# Open_lid.net
KiCad netlist of a schematic drawn in Altium Designer
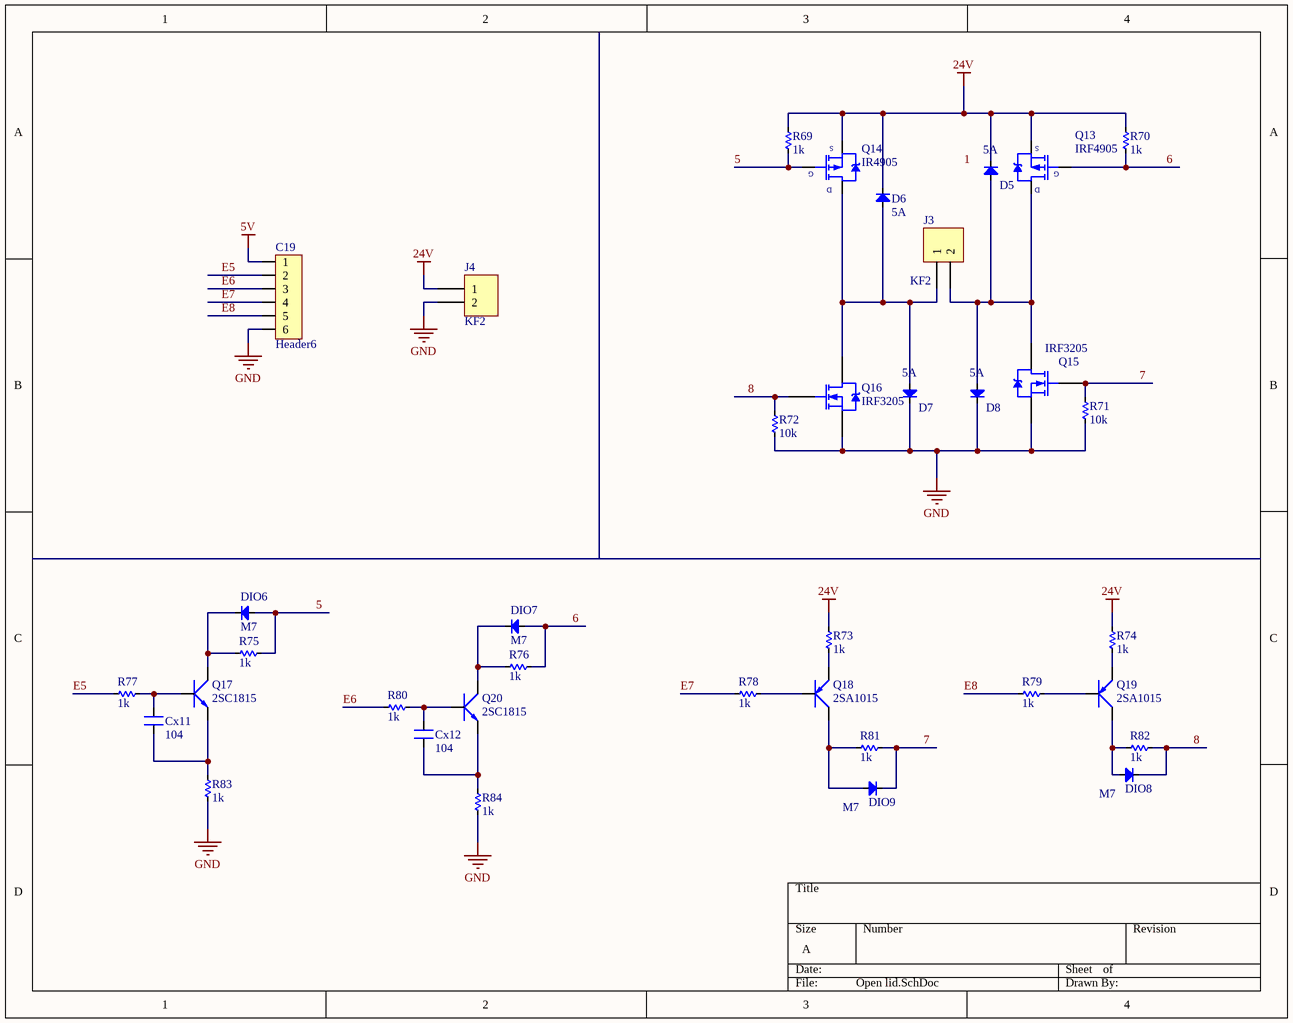
[diagram p0: Open lid.SchDoc]

(export (version "E")
  (design (tool "Eeschema 10.0.6"))
  (components
    (comp (ref "C19")
      (value "Header6")
      (footprint "HDR6")
      (description "Header IDC, 6 x 1 Pin Vertical 2.54mm Pitch (Non-Boxed, Male)")
      (fields
        (field (name "MANUFACTURER") "Würth Elektronik eiSos GmbH")
        (field (name "PARTNO") "613002143121")
        (field (name "CREATED BY") "Karrer Zheng")
      )
      (libsource (lib "LIBRARY") (part "Header6"))
    )
    (comp (ref "Cx11") (value "104") (footprint "CN-SMD-0805") (libsource (lib "LIBRARY") (part "CN")))
    (comp (ref "Cx12") (value "104") (footprint "CN-SMD-0805") (libsource (lib "LIBRARY") (part "CN")))
    (comp (ref "D5")
      (value "5A")
      (footprint "DIO-5A")
      (description "Default Diode")
      (fields (field (name "PUBLISHER") "Altium Limited"))
      (libsource (lib "LIBRARY") (part "Diode"))
    )
    (comp (ref "D6")
      (value "5A")
      (footprint "DIO-5A")
      (description "Default Diode")
      (fields (field (name "PUBLISHER") "Altium Limited"))
      (libsource (lib "LIBRARY") (part "Diode"))
    )
    (comp (ref "D7")
      (value "5A")
      (footprint "DIO-5A")
      (description "Default Diode")
      (fields (field (name "PUBLISHER") "Altium Limited"))
      (libsource (lib "LIBRARY") (part "Diode"))
    )
    (comp (ref "D8")
      (value "5A")
      (footprint "DIO-5A")
      (description "Default Diode")
      (fields (field (name "PUBLISHER") "Altium Limited"))
      (libsource (lib "LIBRARY") (part "Diode"))
    )
    (comp (ref "DIO6")
      (value "M7")
      (footprint "DIO-SMD-106")
      (description "Default Diode")
      (fields (field (name "PUBLISHER") "Altium Limited"))
      (libsource (lib "LIBRARY") (part "Diode SMD"))
    )
    (comp (ref "DIO7")
      (value "M7")
      (footprint "DIO-SMD-106")
      (description "Default Diode")
      (fields (field (name "PUBLISHER") "Altium Limited"))
      (libsource (lib "LIBRARY") (part "Diode SMD"))
    )
    (comp (ref "DIO8")
      (value "M7")
      (footprint "DIO-SMD-106")
      (description "Default Diode")
      (fields (field (name "PUBLISHER") "Altium Limited"))
      (libsource (lib "LIBRARY") (part "Diode SMD"))
    )
    (comp (ref "DIO9")
      (value "M7")
      (footprint "DIO-SMD-106")
      (description "Default Diode")
      (fields (field (name "PUBLISHER") "Altium Limited"))
      (libsource (lib "LIBRARY") (part "Diode SMD"))
    )
    (comp (ref "J3")
      (value "KF2")
      (footprint "KF2-7.62")
      (fields
        (field (name "MANUFACTURER") "Würth Elektronik eiSos GmbH")
        (field (name "PARTNO") "691103110002")
        (field (name "CREATED BY") "Karrer Zheng")
      )
      (libsource (lib "LIBRARY") (part "KF2"))
    )
    (comp (ref "J4")
      (value "KF2")
      (footprint "KF2-7.62")
      (fields
        (field (name "MANUFACTURER") "Würth Elektronik eiSos GmbH")
        (field (name "PARTNO") "691103110002")
        (field (name "CREATED BY") "Karrer Zheng")
      )
      (libsource (lib "") (part "KF2_1"))
    )
    (comp (ref "Q13")
      (value "IRF4905")
      (footprint "TO220-123")
      (description "HEXFET P-Channel Power MOSFET")
      (libsource (lib "LIBRARY") (part "IRF9540"))
    )
    (comp (ref "Q14")
      (value "IR4905")
      (footprint "TO220-123")
      (description "HEXFET P-Channel Power MOSFET")
      (libsource (lib "LIBRARY") (part "IRF9540"))
    )
    (comp (ref "Q15") (value "IRF3205") (footprint "TO220-123") (libsource (lib "LIBRARY") (part "IRFZ44")))
    (comp (ref "Q16") (value "IRF3205") (footprint "TO220-123") (libsource (lib "LIBRARY") (part "IRFZ44")))
    (comp (ref "Q17")
      (value "2SC1815")
      (footprint "SOT23-321")
      (description "NPN 600mW, ECB")
      (libsource (lib "LIBRARY") (part "2SC1815"))
    )
    (comp (ref "Q18")
      (value "2SA1015")
      (footprint "SOT23-321")
      (description "PNP 600mW, ECB")
      (libsource (lib "LIBRARY") (part "2SA1015"))
    )
    (comp (ref "Q19")
      (value "2SA1015")
      (footprint "SOT23-321")
      (description "PNP 600mW, ECB")
      (libsource (lib "LIBRARY") (part "2SA1015"))
    )
    (comp (ref "Q20")
      (value "2SC1815")
      (footprint "SOT23-321")
      (description "NPN 600mW, ECB")
      (libsource (lib "LIBRARY") (part "2SC1815"))
    )
    (comp (ref "R69")
      (value "1k")
      (footprint "RES-1/4W-SMALL")
      (description "Res")
      (fields
        (field (name "MANUFACTURER") "Generic Components")
        (field (name "PUBLISHER") "Altium Hobart Technology Centre")
      )
      (libsource (lib "LIBRARY") (part "Res"))
    )
    (comp (ref "R70")
      (value "1k")
      (footprint "RES-1/4W-SMALL")
      (description "Res")
      (fields
        (field (name "MANUFACTURER") "Generic Components")
        (field (name "PUBLISHER") "Altium Hobart Technology Centre")
      )
      (libsource (lib "LIBRARY") (part "Res"))
    )
    (comp (ref "R71")
      (value "10k")
      (footprint "RES-1/4W-SMALL")
      (description "Res")
      (fields
        (field (name "MANUFACTURER") "Generic Components")
        (field (name "PUBLISHER") "Altium Hobart Technology Centre")
      )
      (libsource (lib "LIBRARY") (part "Res"))
    )
    (comp (ref "R72")
      (value "10k")
      (footprint "RES-1/4W-SMALL")
      (description "Res")
      (fields
        (field (name "MANUFACTURER") "Generic Components")
        (field (name "PUBLISHER") "Altium Hobart Technology Centre")
      )
      (libsource (lib "LIBRARY") (part "Res"))
    )
    (comp (ref "R73")
      (value "1k")
      (footprint "RES-SMD-0805")
      (description "Resistor")
      (fields
        (field (name "MANUFACTURER") "Generic Components")
        (field (name "PUBLISHER") "Altium Hobart Technology Centre")
      )
      (libsource (lib "LIBRARY") (part "Res-SMD"))
    )
    (comp (ref "R74")
      (value "1k")
      (footprint "RES-SMD-0805")
      (description "Resistor")
      (fields
        (field (name "MANUFACTURER") "Generic Components")
        (field (name "PUBLISHER") "Altium Hobart Technology Centre")
      )
      (libsource (lib "LIBRARY") (part "Res-SMD"))
    )
    (comp (ref "R75")
      (value "1k")
      (footprint "RES-SMD-0805")
      (description "Resistor")
      (fields
        (field (name "MANUFACTURER") "Generic Components")
        (field (name "PUBLISHER") "Altium Hobart Technology Centre")
      )
      (libsource (lib "LIBRARY") (part "Res-SMD"))
    )
    (comp (ref "R76")
      (value "1k")
      (footprint "RES-SMD-0805")
      (description "Resistor")
      (fields
        (field (name "MANUFACTURER") "Generic Components")
        (field (name "PUBLISHER") "Altium Hobart Technology Centre")
      )
      (libsource (lib "LIBRARY") (part "Res-SMD"))
    )
    (comp (ref "R77")
      (value "1k")
      (footprint "RES-SMD-0805")
      (description "Resistor")
      (fields
        (field (name "MANUFACTURER") "Generic Components")
        (field (name "PUBLISHER") "Altium Hobart Technology Centre")
      )
      (libsource (lib "LIBRARY") (part "Res-SMD"))
    )
    (comp (ref "R78")
      (value "1k")
      (footprint "RES-SMD-0805")
      (description "Resistor")
      (fields
        (field (name "MANUFACTURER") "Generic Components")
        (field (name "PUBLISHER") "Altium Hobart Technology Centre")
      )
      (libsource (lib "LIBRARY") (part "Res-SMD"))
    )
    (comp (ref "R79")
      (value "1k")
      (footprint "RES-SMD-0805")
      (description "Resistor")
      (fields
        (field (name "MANUFACTURER") "Generic Components")
        (field (name "PUBLISHER") "Altium Hobart Technology Centre")
      )
      (libsource (lib "LIBRARY") (part "Res-SMD"))
    )
    (comp (ref "R80")
      (value "1k")
      (footprint "RES-SMD-0805")
      (description "Resistor")
      (fields
        (field (name "MANUFACTURER") "Generic Components")
        (field (name "PUBLISHER") "Altium Hobart Technology Centre")
      )
      (libsource (lib "LIBRARY") (part "Res-SMD"))
    )
    (comp (ref "R81")
      (value "1k")
      (footprint "RES-SMD-0805")
      (description "Resistor")
      (fields
        (field (name "MANUFACTURER") "Generic Components")
        (field (name "PUBLISHER") "Altium Hobart Technology Centre")
      )
      (libsource (lib "LIBRARY") (part "Res-SMD"))
    )
    (comp (ref "R82")
      (value "1k")
      (footprint "RES-SMD-0805")
      (description "Resistor")
      (fields
        (field (name "MANUFACTURER") "Generic Components")
        (field (name "PUBLISHER") "Altium Hobart Technology Centre")
      )
      (libsource (lib "LIBRARY") (part "Res-SMD"))
    )
    (comp (ref "R83")
      (value "1k")
      (footprint "RES-SMD-0805")
      (description "Resistor")
      (fields
        (field (name "MANUFACTURER") "Generic Components")
        (field (name "PUBLISHER") "Altium Hobart Technology Centre")
      )
      (libsource (lib "LIBRARY") (part "Res-SMD"))
    )
    (comp (ref "R84")
      (value "1k")
      (footprint "RES-SMD-0805")
      (description "Resistor")
      (fields
        (field (name "MANUFACTURER") "Generic Components")
        (field (name "PUBLISHER") "Altium Hobart Technology Centre")
      )
      (libsource (lib "LIBRARY") (part "Res-SMD"))
    )
  )
  (nets
    (net (code "2") (name "/5") (class "Default")
      (node (ref "DIO6") (pin "1") (pinfunction "A_1") (pintype "passive"))
      (node (ref "Q14") (pin "1") (pinfunction "G_1") (pintype "passive"))
      (node (ref "R69") (pin "2") (pinfunction "2_2") (pintype "passive"))
      (node (ref "R75") (pin "1") (pinfunction "1_1") (pintype "passive"))
    )
    (net (code "3") (name "/6") (class "Default")
      (node (ref "DIO7") (pin "1") (pinfunction "A_1") (pintype "passive"))
      (node (ref "Q13") (pin "1") (pinfunction "G_1") (pintype "passive"))
      (node (ref "R70") (pin "2") (pinfunction "2_2") (pintype "passive"))
      (node (ref "R76") (pin "1") (pinfunction "1_1") (pintype "passive"))
    )
    (net (code "4") (name "/7") (class "Default")
      (node (ref "DIO9") (pin "2") (pinfunction "K_2") (pintype "passive"))
      (node (ref "Q15") (pin "1") (pinfunction "G_1") (pintype "passive"))
      (node (ref "R71") (pin "1") (pinfunction "1_1") (pintype "passive"))
      (node (ref "R81") (pin "1") (pinfunction "1_1") (pintype "passive"))
    )
    (net (code "5") (name "/8") (class "Default")
      (node (ref "DIO8") (pin "2") (pinfunction "K_2") (pintype "passive"))
      (node (ref "Q16") (pin "1") (pinfunction "G_1") (pintype "passive"))
      (node (ref "R72") (pin "1") (pinfunction "1_1") (pintype "passive"))
      (node (ref "R82") (pin "1") (pinfunction "1_1") (pintype "passive"))
    )
    (net (code "6") (name "/E5") (class "Default")
      (node (ref "C19") (pin "2") (pinfunction "2_2") (pintype "passive"))
      (node (ref "R77") (pin "2") (pinfunction "2_2") (pintype "passive"))
    )
    (net (code "7") (name "/E6") (class "Default")
      (node (ref "C19") (pin "3") (pinfunction "3_3") (pintype "passive"))
      (node (ref "R80") (pin "2") (pinfunction "2_2") (pintype "passive"))
    )
    (net (code "8") (name "/E7") (class "Default")
      (node (ref "C19") (pin "4") (pinfunction "4_4") (pintype "passive"))
      (node (ref "R78") (pin "2") (pinfunction "2_2") (pintype "passive"))
    )
    (net (code "9") (name "/E8") (class "Default")
      (node (ref "C19") (pin "5") (pinfunction "5_5") (pintype "passive"))
      (node (ref "R79") (pin "2") (pinfunction "2_2") (pintype "passive"))
    )
    (net (code "10") (name "5V") (class "Default")
      (node (ref "C19") (pin "1") (pinfunction "1_1") (pintype "passive"))
    )
    (net (code "11") (name "24V") (class "Default")
      (node (ref "D5") (pin "2") (pinfunction "K_2") (pintype "passive"))
      (node (ref "D6") (pin "2") (pinfunction "K_2") (pintype "passive"))
      (node (ref "J4") (pin "1") (pinfunction "1_1") (pintype "passive"))
      (node (ref "Q13") (pin "3") (pinfunction "S_3") (pintype "passive"))
      (node (ref "Q14") (pin "3") (pinfunction "S_3") (pintype "passive"))
      (node (ref "R69") (pin "1") (pinfunction "1_1") (pintype "passive"))
      (node (ref "R70") (pin "1") (pinfunction "1_1") (pintype "passive"))
      (node (ref "R73") (pin "1") (pinfunction "1_1") (pintype "passive"))
      (node (ref "R74") (pin "1") (pinfunction "1_1") (pintype "passive"))
    )
    (net (code "12") (name "GND") (class "Default")
      (node (ref "C19") (pin "6") (pinfunction "6_6") (pintype "passive"))
      (node (ref "D7") (pin "2") (pinfunction "K_2") (pintype "passive"))
      (node (ref "D8") (pin "2") (pinfunction "K_2") (pintype "passive"))
      (node (ref "J4") (pin "2") (pinfunction "2_2") (pintype "passive"))
      (node (ref "Q15") (pin "3") (pinfunction "S_3") (pintype "passive"))
      (node (ref "Q16") (pin "3") (pinfunction "S_3") (pintype "passive"))
      (node (ref "R71") (pin "2") (pinfunction "2_2") (pintype "passive"))
      (node (ref "R72") (pin "2") (pinfunction "2_2") (pintype "passive"))
      (node (ref "R83") (pin "2") (pinfunction "2_2") (pintype "passive"))
      (node (ref "R84") (pin "2") (pinfunction "2_2") (pintype "passive"))
    )
    (net (code "13") (name "Net-(D5-A)") (class "Default")
      (node (ref "D5") (pin "1") (pinfunction "A_1") (pintype "passive"))
      (node (ref "D8") (pin "1") (pinfunction "A_1") (pintype "passive"))
      (node (ref "J3") (pin "2") (pinfunction "2_2") (pintype "passive"))
      (node (ref "Q13") (pin "2") (pinfunction "D_2") (pintype "passive"))
      (node (ref "Q15") (pin "2") (pinfunction "D_2") (pintype "passive"))
    )
    (net (code "14") (name "Net-(D6-A)") (class "Default")
      (node (ref "D6") (pin "1") (pinfunction "A_1") (pintype "passive"))
      (node (ref "D7") (pin "1") (pinfunction "A_1") (pintype "passive"))
      (node (ref "J3") (pin "1") (pinfunction "1_1") (pintype "passive"))
      (node (ref "Q14") (pin "2") (pinfunction "D_2") (pintype "passive"))
      (node (ref "Q16") (pin "2") (pinfunction "D_2") (pintype "passive"))
    )
    (net (code "15") (name "Net-(DIO6-K)") (class "Default")
      (node (ref "DIO6") (pin "2") (pinfunction "K_2") (pintype "passive"))
      (node (ref "Q17") (pin "2") (pinfunction "C_2") (pintype "passive"))
      (node (ref "R75") (pin "2") (pinfunction "2_2") (pintype "passive"))
    )
    (net (code "16") (name "Net-(DIO7-K)") (class "Default")
      (node (ref "DIO7") (pin "2") (pinfunction "K_2") (pintype "passive"))
      (node (ref "Q20") (pin "2") (pinfunction "C_2") (pintype "passive"))
      (node (ref "R76") (pin "2") (pinfunction "2_2") (pintype "passive"))
    )
    (net (code "17") (name "Net-(DIO8-A)") (class "Default")
      (node (ref "DIO8") (pin "1") (pinfunction "A_1") (pintype "passive"))
      (node (ref "Q19") (pin "2") (pinfunction "C_2") (pintype "passive"))
      (node (ref "R82") (pin "2") (pinfunction "2_2") (pintype "passive"))
    )
    (net (code "18") (name "Net-(DIO9-A)") (class "Default")
      (node (ref "DIO9") (pin "1") (pinfunction "A_1") (pintype "passive"))
      (node (ref "Q18") (pin "2") (pinfunction "C_2") (pintype "passive"))
      (node (ref "R81") (pin "2") (pinfunction "2_2") (pintype "passive"))
    )
    (net (code "19") (name "Net-(Q17-B)") (class "Default")
      (node (ref "Cx11") (pin "2") (pinfunction "2_2") (pintype "passive"))
      (node (ref "Q17") (pin "3") (pinfunction "B_3") (pintype "passive"))
      (node (ref "R77") (pin "1") (pinfunction "1_1") (pintype "passive"))
    )
    (net (code "20") (name "Net-(Q17-E)") (class "Default")
      (node (ref "Cx11") (pin "1") (pinfunction "1_1") (pintype "passive"))
      (node (ref "Q17") (pin "1") (pinfunction "E_1") (pintype "passive"))
      (node (ref "R83") (pin "1") (pinfunction "1_1") (pintype "passive"))
    )
    (net (code "21") (name "Net-(Q18-B)") (class "Default")
      (node (ref "Q18") (pin "3") (pinfunction "B_3") (pintype "passive"))
      (node (ref "R78") (pin "1") (pinfunction "1_1") (pintype "passive"))
    )
    (net (code "22") (name "Net-(Q18-E)") (class "Default")
      (node (ref "Q18") (pin "1") (pinfunction "E_1") (pintype "passive"))
      (node (ref "R73") (pin "2") (pinfunction "2_2") (pintype "passive"))
    )
    (net (code "23") (name "Net-(Q19-B)") (class "Default")
      (node (ref "Q19") (pin "3") (pinfunction "B_3") (pintype "passive"))
      (node (ref "R79") (pin "1") (pinfunction "1_1") (pintype "passive"))
    )
    (net (code "24") (name "Net-(Q19-E)") (class "Default")
      (node (ref "Q19") (pin "1") (pinfunction "E_1") (pintype "passive"))
      (node (ref "R74") (pin "2") (pinfunction "2_2") (pintype "passive"))
    )
    (net (code "25") (name "Net-(Q20-B)") (class "Default")
      (node (ref "Cx12") (pin "2") (pinfunction "2_2") (pintype "passive"))
      (node (ref "Q20") (pin "3") (pinfunction "B_3") (pintype "passive"))
      (node (ref "R80") (pin "1") (pinfunction "1_1") (pintype "passive"))
    )
    (net (code "26") (name "Net-(Q20-E)") (class "Default")
      (node (ref "Cx12") (pin "1") (pinfunction "1_1") (pintype "passive"))
      (node (ref "Q20") (pin "1") (pinfunction "E_1") (pintype "passive"))
      (node (ref "R84") (pin "1") (pinfunction "1_1") (pintype "passive"))
    )
  )
)
